# COMS0004_SwC_Main.net
KiCad netlist of a schematic drawn in Altium Designer
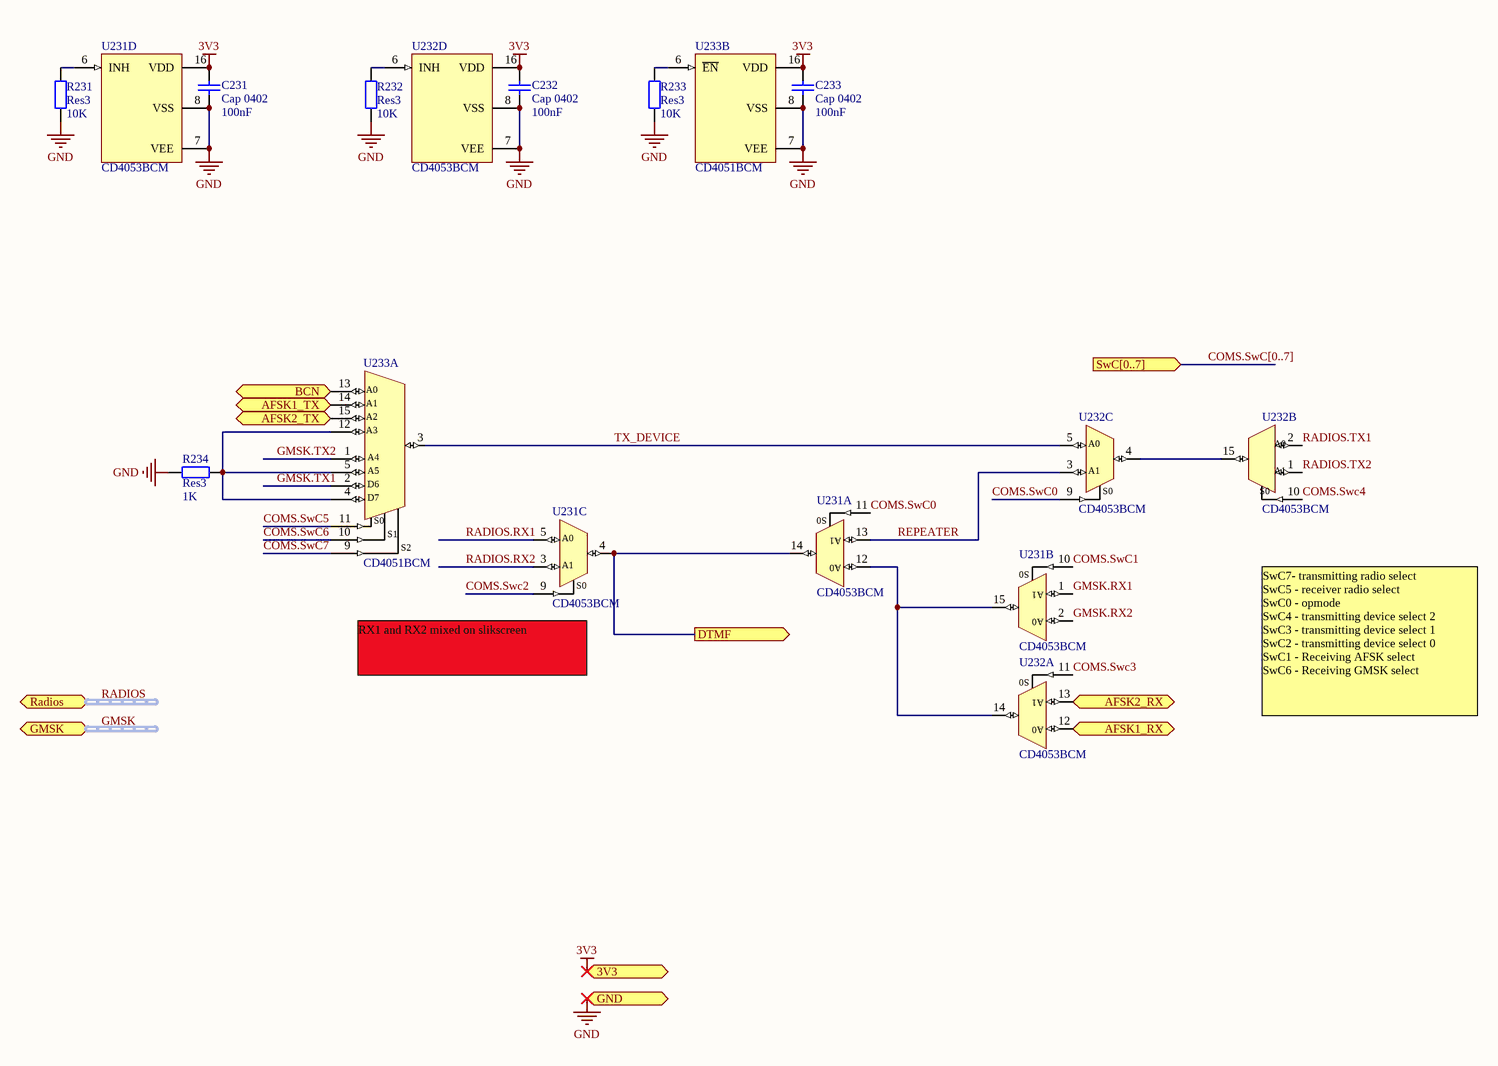
[diagram p0: COMS0004 SwC_Main.SchDoc]

(export (version "E")
  (design (tool "Eeschema 10.0.6"))
  (components
    (comp (ref "C231")
      (value "Cap 0402")
      (footprint "CAPC1005X06L")
      (description "Capacitor")
      (fields (field (name "ALTIUM_VALUE") "100nF") (field (name "PUBLISHER") "Altium Limited"))
      (libsource (lib "CSC") (part "Cap 0402"))
    )
    (comp (ref "C232")
      (value "Cap 0402")
      (footprint "CAPC1005X06L")
      (description "Capacitor")
      (fields (field (name "ALTIUM_VALUE") "100nF") (field (name "PUBLISHER") "Altium Limited"))
      (libsource (lib "CSC") (part "Cap 0402"))
    )
    (comp (ref "C233")
      (value "Cap 0402")
      (footprint "CAPC1005X06L")
      (description "Capacitor")
      (fields (field (name "ALTIUM_VALUE") "100nF") (field (name "PUBLISHER") "Altium Limited"))
      (libsource (lib "CSC") (part "Cap 0402"))
    )
    (comp (ref "R231")
      (value "Res3")
      (footprint "RESC1005X06L")
      (description "Resistor")
      (fields (field (name "ALTIUM_VALUE") "10K") (field (name "PUBLISHER") "Altium Limited"))
      (libsource (lib "CSC") (part "Res3"))
    )
    (comp (ref "R232")
      (value "Res3")
      (footprint "RESC1005X06L")
      (description "Resistor")
      (fields (field (name "ALTIUM_VALUE") "10K") (field (name "PUBLISHER") "Altium Limited"))
      (libsource (lib "CSC") (part "Res3"))
    )
    (comp (ref "R233")
      (value "Res3")
      (footprint "RESC1005X06L")
      (description "Resistor")
      (fields (field (name "ALTIUM_VALUE") "10K") (field (name "PUBLISHER") "Altium Limited"))
      (libsource (lib "CSC") (part "Res3"))
    )
    (comp (ref "R234")
      (value "Res3")
      (footprint "RESC1005X06L")
      (description "Resistor")
      (fields (field (name "ALTIUM_VALUE") "1K") (field (name "PUBLISHER") "Altium Limited"))
      (libsource (lib "") (part "Res3_1"))
    )
    (comp (ref "U231")
      (value "CD4053BCM")
      (footprint "Comms Board Small Footprints:TSSOP16")
      (description "Triple 2-Channnel Analog Multiplexer/Demutiplexer")
      (libsource (lib "") (part "CD4053BCM_1"))
    )
    (comp (ref "U232")
      (value "CD4053BCM")
      (footprint "Comms Board Small Footprints:TSSOP16")
      (description "Triple 2-Channnel Analog Multiplexer/Demutiplexer")
      (libsource (lib "Comms Board Small Footprints") (part "CD4053BCM"))
    )
    (comp (ref "U233")
      (value "CD4051BCM")
      (footprint "Comms Board Small Footprints:TSSOP16")
      (description "8-Channel Analog Multiplexer/Demultiplexer")
      (libsource (lib "Comms Board Small Footprints") (part "CD4051BCM"))
    )
  )
  (nets
    (net (code "6") (name "/AFSK1_RX") (class "Default")
      (node (ref "U232") (pin "12") (pinfunction "A0_12") (pintype "bidirectional"))
    )
    (net (code "7") (name "/AFSK1_TX") (class "Default")
      (node (ref "U233") (pin "14") (pinfunction "A1_14") (pintype "bidirectional"))
    )
    (net (code "8") (name "/AFSK2_RX") (class "Default")
      (node (ref "U232") (pin "13") (pinfunction "A1_13") (pintype "bidirectional"))
    )
    (net (code "9") (name "/AFSK2_TX") (class "Default")
      (node (ref "U233") (pin "15") (pinfunction "A2_15") (pintype "bidirectional"))
    )
    (net (code "10") (name "/BCN") (class "Default")
      (node (ref "U233") (pin "13") (pinfunction "A0_13") (pintype "bidirectional"))
    )
    (net (code "11") (name "/COMS.SwC0") (class "Default")
      (node (ref "U231") (pin "11") (pinfunction "A_11") (pintype "input"))
      (node (ref "U232") (pin "9") (pinfunction "C_9") (pintype "input"))
    )
    (net (code "12") (name "/COMS.SwC1") (class "Default")
      (node (ref "U231") (pin "10") (pinfunction "B_10") (pintype "input"))
    )
    (net (code "13") (name "/COMS.SwC5") (class "Default")
      (node (ref "U233") (pin "11") (pinfunction "S0_11") (pintype "input"))
    )
    (net (code "14") (name "/COMS.SwC6") (class "Default")
      (node (ref "U233") (pin "10") (pinfunction "S1_10") (pintype "input"))
    )
    (net (code "15") (name "/COMS.SwC7") (class "Default")
      (node (ref "U233") (pin "9") (pinfunction "S2_9") (pintype "input"))
    )
    (net (code "17") (name "/COMS.Swc2") (class "Default")
      (node (ref "U231") (pin "9") (pinfunction "C_9") (pintype "input"))
    )
    (net (code "18") (name "/COMS.Swc3") (class "Default")
      (node (ref "U232") (pin "11") (pinfunction "A_11") (pintype "input"))
    )
    (net (code "19") (name "/COMS.Swc4") (class "Default")
      (node (ref "U232") (pin "10") (pinfunction "B_10") (pintype "input"))
    )
    (net (code "20") (name "/DTMF") (class "Default")
      (node (ref "U231") (pin "14") (pinfunction "A_out_14") (pintype "bidirectional"))
      (node (ref "U231") (pin "4") (pinfunction "c_out_4") (pintype "bidirectional"))
    )
    (net (code "21") (name "/GMSK.RX1") (class "Default")
      (node (ref "U231") (pin "1") (pinfunction "by_1") (pintype "bidirectional"))
    )
    (net (code "22") (name "/GMSK.RX2") (class "Default")
      (node (ref "U231") (pin "2") (pinfunction "bx_2") (pintype "bidirectional"))
    )
    (net (code "23") (name "/GMSK.TX1") (class "Default")
      (node (ref "U233") (pin "2") (pinfunction "A6_2") (pintype "bidirectional"))
    )
    (net (code "24") (name "/GMSK.TX2") (class "Default")
      (node (ref "U233") (pin "1") (pinfunction "A4_1") (pintype "bidirectional"))
    )
    (net (code "25") (name "/RADIOS.RX1") (class "Default")
      (node (ref "U231") (pin "5") (pinfunction "cx_5") (pintype "bidirectional"))
    )
    (net (code "26") (name "/RADIOS.RX2") (class "Default")
      (node (ref "U231") (pin "3") (pinfunction "cy_3") (pintype "bidirectional"))
    )
    (net (code "27") (name "/RADIOS.TX1") (class "Default")
      (node (ref "U232") (pin "2") (pinfunction "bx_2") (pintype "bidirectional"))
    )
    (net (code "28") (name "/RADIOS.TX2") (class "Default")
      (node (ref "U232") (pin "1") (pinfunction "by_1") (pintype "bidirectional"))
    )
    (net (code "29") (name "/REPEATER") (class "Default")
      (node (ref "U231") (pin "13") (pinfunction "A1_13") (pintype "bidirectional"))
      (node (ref "U232") (pin "3") (pinfunction "cy_3") (pintype "bidirectional"))
    )
    (net (code "30") (name "/TX_DEVICE") (class "Default")
      (node (ref "U232") (pin "5") (pinfunction "cx_5") (pintype "bidirectional"))
      (node (ref "U233") (pin "3") (pinfunction "O_3") (pintype "bidirectional"))
    )
    (net (code "33") (name "3V3") (class "Default")
      (node (ref "C231") (pin "2") (pinfunction "2_2") (pintype "passive"))
      (node (ref "C232") (pin "2") (pinfunction "2_2") (pintype "passive"))
      (node (ref "C233") (pin "2") (pinfunction "2_2") (pintype "passive"))
      (node (ref "U231") (pin "16") (pinfunction "VDD_16") (pintype "power_in"))
      (node (ref "U232") (pin "16") (pinfunction "VDD_16") (pintype "power_in"))
      (node (ref "U233") (pin "16") (pinfunction "VDD_16") (pintype "power_in"))
    )
    (net (code "34") (name "GND") (class "Default")
      (node (ref "C231") (pin "1") (pinfunction "1_1") (pintype "passive"))
      (node (ref "C232") (pin "1") (pinfunction "1_1") (pintype "passive"))
      (node (ref "C233") (pin "1") (pinfunction "1_1") (pintype "passive"))
      (node (ref "R231") (pin "2") (pinfunction "2_2") (pintype "passive"))
      (node (ref "R232") (pin "2") (pinfunction "2_2") (pintype "passive"))
      (node (ref "R233") (pin "2") (pinfunction "2_2") (pintype "passive"))
      (node (ref "R234") (pin "1") (pinfunction "1_1") (pintype "passive"))
      (node (ref "U231") (pin "7") (pinfunction "VEE_7") (pintype "power_in"))
      (node (ref "U231") (pin "8") (pinfunction "VSS_8") (pintype "power_in"))
      (node (ref "U232") (pin "7") (pinfunction "VEE_7") (pintype "power_in"))
      (node (ref "U232") (pin "8") (pinfunction "VSS_8") (pintype "power_in"))
      (node (ref "U233") (pin "7") (pinfunction "VEE_7") (pintype "power_in"))
      (node (ref "U233") (pin "8") (pinfunction "VSS_8") (pintype "power_in"))
    )
    (net (code "35") (name "Net-(U231A-A0)") (class "Default")
      (node (ref "U231") (pin "12") (pinfunction "A0_12") (pintype "bidirectional"))
      (node (ref "U231") (pin "15") (pinfunction "b_out_15") (pintype "bidirectional"))
      (node (ref "U232") (pin "14") (pinfunction "A_out_14") (pintype "bidirectional"))
    )
    (net (code "36") (name "Net-(U231D-INH)") (class "Default")
      (node (ref "R231") (pin "1") (pinfunction "1_1") (pintype "passive"))
      (node (ref "U231") (pin "6") (pinfunction "INH_6") (pintype "input"))
    )
    (net (code "37") (name "Net-(U232B-b_out)") (class "Default")
      (node (ref "U232") (pin "15") (pinfunction "b_out_15") (pintype "bidirectional"))
      (node (ref "U232") (pin "4") (pinfunction "c_out_4") (pintype "bidirectional"))
    )
    (net (code "38") (name "Net-(U232D-INH)") (class "Default")
      (node (ref "R232") (pin "1") (pinfunction "1_1") (pintype "passive"))
      (node (ref "U232") (pin "6") (pinfunction "INH_6") (pintype "input"))
    )
    (net (code "39") (name "Net-(U233A-A3)") (class "Default")
      (node (ref "R234") (pin "2") (pinfunction "2_2") (pintype "passive"))
      (node (ref "U233") (pin "12") (pinfunction "A3_12") (pintype "bidirectional"))
      (node (ref "U233") (pin "4") (pinfunction "A7_4") (pintype "bidirectional"))
      (node (ref "U233") (pin "5") (pinfunction "A5_5") (pintype "bidirectional"))
    )
    (net (code "40") (name "Net-(U233B-~{EN})") (class "Default")
      (node (ref "R233") (pin "1") (pinfunction "1_1") (pintype "passive"))
      (node (ref "U233") (pin "6") (pinfunction "~{EN}_6") (pintype "input"))
    )
  )
)
